# Lin-reg.net
KiCad netlist of a schematic drawn in Altium Designer
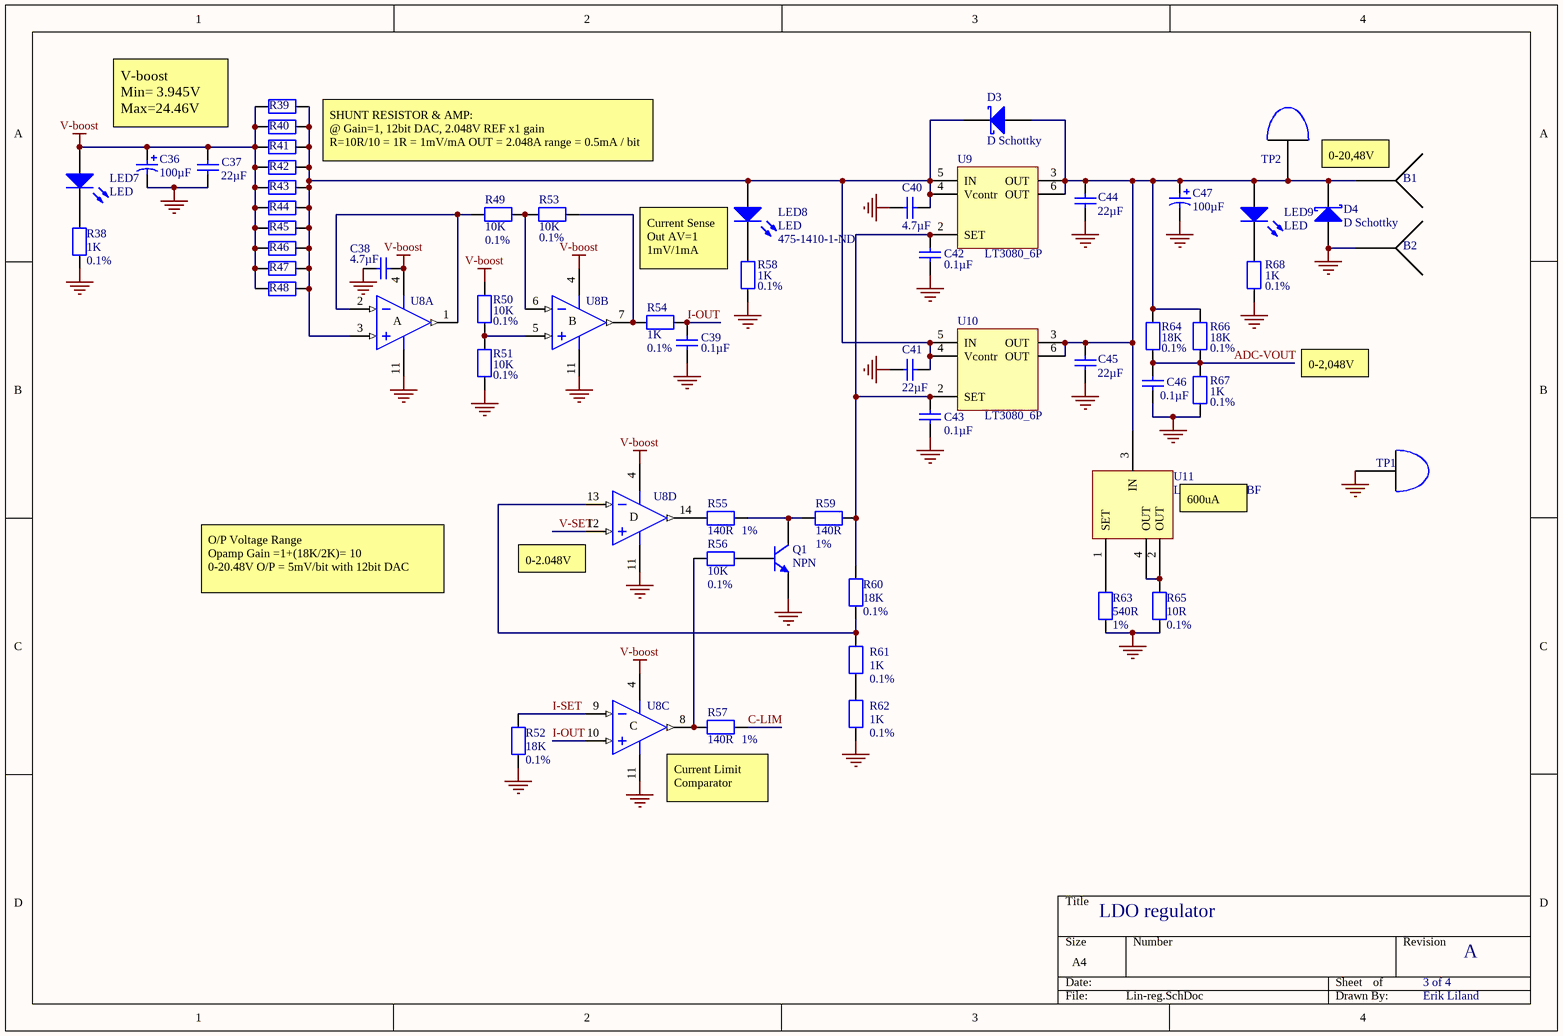
[diagram p0: Lin-reg.SchDoc]

(export (version "E")
  (design (tool "Eeschema 10.0.6"))
  (components
    (comp (ref "B1")
      (value "Banana socket pcb")
      (footprint "BatteruPSU:PCB Banana jack red")
      (description "2.54mm skrew terminal")
      (libsource (lib "BatteryPSU-parts") (part "Banana socket pcb"))
    )
    (comp (ref "B2")
      (value "Banana socket pcb")
      (footprint "BatteruPSU:PCB Banana jack black")
      (description "2.54mm skrew terminal")
      (libsource (lib "BatteryPSU-parts") (part "Banana socket pcb"))
    )
    (comp (ref "C36")
      (value "100µF")
      (footprint "BatteruPSU:CAP SMD (F)")
      (description "Polarized Capacitor")
      (fields
        (field (name "MANUFACTURER") "Panasonic Electronic Components")
        (field (name "MANUFACTURER PART NUMBER") "EEH-ZA1H101P")
      )
      (libsource (lib "BatteryPSU-parts") (part "Cap Pol"))
    )
    (comp (ref "C37")
      (value "22µF")
      (footprint "BatteruPSU:0805_N_CAP")
      (description "Capacitor")
      (fields
        (field (name "MANUFACTURER") "TDK Corporation")
        (field (name "MANUFACTURER PART NUMBER") "C2012X5R1V226M125AC")
      )
      (libsource (lib "BatteryPSU-parts") (part "Cap"))
    )
    (comp (ref "C38")
      (value "4.7µF")
      (footprint "BatteruPSU:0805_N_CAP")
      (description "Capacitor")
      (fields
        (field (name "MANUFACTURER") "Samsung Electro-Mechanics America, Inc")
        (field (name "MANUFACTURER PART NUMBER") "CL21B475KOFNFNE")
      )
      (libsource (lib "BatteryPSU-parts") (part "Cap"))
    )
    (comp (ref "C39")
      (value "0.1µF")
      (footprint "BatteruPSU:0805_N_CAP")
      (description "Capacitor")
      (fields
        (field (name "MANUFACTURER") "Kemet")
        (field (name "MANUFACTURER PART NUMBER") "C0805C104K4RACTU")
      )
      (libsource (lib "BatteryPSU-parts") (part "Cap"))
    )
    (comp (ref "C40")
      (value "4.7µF")
      (footprint "BatteruPSU:0805_N_CAP")
      (description "Capacitor")
      (fields
        (field (name "MANUFACTURER") "Samsung Electro-Mechanics America, Inc")
        (field (name "MANUFACTURER PART NUMBER") "CL21B475KOFNFNE")
      )
      (libsource (lib "BatteryPSU-parts") (part "Cap"))
    )
    (comp (ref "C41")
      (value "22µF")
      (footprint "BatteruPSU:0805_N_CAP")
      (description "Capacitor")
      (fields
        (field (name "MANUFACTURER") "TDK Corporation")
        (field (name "MANUFACTURER PART NUMBER") "C2012X5R1V226M125AC")
      )
      (libsource (lib "BatteryPSU-parts") (part "Cap"))
    )
    (comp (ref "C42")
      (value "0.1µF")
      (footprint "BatteruPSU:0805_N_CAP")
      (description "Capacitor")
      (fields
        (field (name "MANUFACTURER") "Kemet")
        (field (name "MANUFACTURER PART NUMBER") "C0805C104K4RACTU")
      )
      (libsource (lib "BatteryPSU-parts") (part "Cap"))
    )
    (comp (ref "C43")
      (value "0.1µF")
      (footprint "BatteruPSU:0805_N_CAP")
      (description "Capacitor")
      (fields
        (field (name "MANUFACTURER") "Kemet")
        (field (name "MANUFACTURER PART NUMBER") "C0805C104K4RACTU")
      )
      (libsource (lib "BatteryPSU-parts") (part "Cap"))
    )
    (comp (ref "C44")
      (value "22µF")
      (footprint "BatteruPSU:0805_N_CAP")
      (description "Capacitor")
      (fields
        (field (name "MANUFACTURER") "TDK Corporation")
        (field (name "MANUFACTURER PART NUMBER") "C2012X5R1V226M125AC")
      )
      (libsource (lib "BatteryPSU-parts") (part "Cap"))
    )
    (comp (ref "C45")
      (value "22µF")
      (footprint "BatteruPSU:0805_N_CAP")
      (description "Capacitor")
      (fields
        (field (name "MANUFACTURER") "TDK Corporation")
        (field (name "MANUFACTURER PART NUMBER") "C2012X5R1V226M125AC")
      )
      (libsource (lib "BatteryPSU-parts") (part "Cap"))
    )
    (comp (ref "C46")
      (value "0.1µF")
      (footprint "BatteruPSU:0805_N_CAP")
      (description "Capacitor")
      (fields
        (field (name "MANUFACTURER") "Kemet")
        (field (name "MANUFACTURER PART NUMBER") "C0805C104K4RACTU")
      )
      (libsource (lib "BatteryPSU-parts") (part "Cap"))
    )
    (comp (ref "C47")
      (value "100µF")
      (footprint "BatteruPSU:CAP SMD (F)")
      (description "Polarized Capacitor")
      (fields
        (field (name "MANUFACTURER") "Panasonic Electronic Components")
        (field (name "MANUFACTURER PART NUMBER") "EEH-ZA1H101P")
      )
      (libsource (lib "BatteryPSU-parts") (part "Cap Pol"))
    )
    (comp (ref "D3")
      (value "D Schottky")
      (footprint "DO-214AC, SMA")
      (description "Schottky Diode")
      (fields
        (field (name "MANUFACTURER") "Micro Commercial Co")
        (field (name "MANUFACTURER PART NUMBER") "SK33A-TP")
        (field (name "PUBLISHER") "Altium Limited")
      )
      (libsource (lib "BatteryPSU-parts") (part "D Schottky"))
    )
    (comp (ref "D4")
      (value "D Schottky")
      (footprint "DO-214AC, SMA")
      (description "Schottky Diode")
      (fields
        (field (name "MANUFACTURER") "Micro Commercial Co")
        (field (name "MANUFACTURER PART NUMBER") "SK33A-TP")
        (field (name "PUBLISHER") "Altium Limited")
      )
      (libsource (lib "BatteryPSU-parts") (part "D Schottky"))
    )
    (comp (ref "LED7")
      (value "LED")
      (footprint "BatteruPSU:0805_N_LED")
      (description "Typical RED, GREEN, YELLOW, AMBER")
      (fields
        (field (name "MANUFACTURER") "OSRAM Opto Semiconductors Inc")
        (field (name "MANUFACTURER PART NUMBER") "LG R971-KN-1")
      )
      (libsource (lib "BatteryPSU-parts") (part "LED"))
    )
    (comp (ref "LED8")
      (value "LED")
      (footprint "BatteruPSU:0805_N_LED")
      (description "Typical RED, GREEN, YELLOW, AMBER")
      (fields
        (field (name "SUPPLIER PART NUMBER 1") "475-1410-1-ND")
        (field (name "MANUFACTURER") "OSRAM Opto Semiconductors Inc")
        (field (name "MANUFACTURER PART NUMBER") "LG R971-KN-1")
      )
      (libsource (lib "BatteryPSU-parts") (part "LED"))
    )
    (comp (ref "LED9")
      (value "LED")
      (footprint "BatteruPSU:0805_N_LED")
      (description "Typical RED, GREEN, YELLOW, AMBER")
      (fields
        (field (name "MANUFACTURER") "OSRAM Opto Semiconductors Inc")
        (field (name "MANUFACTURER PART NUMBER") "LG R971-KN-1")
      )
      (libsource (lib "BatteryPSU-parts") (part "LED"))
    )
    (comp (ref "Q1")
      (value "NPN")
      (footprint "BatteruPSU:SOT-23_N")
      (description "NPN General Purpose Amplifier")
      (fields
        (field (name "MANUFACTURER") "Micro Commercial Co")
        (field (name "MANUFACTURER PART NUMBER") "MMBT3904-TP")
      )
      (libsource (lib "BatteryPSU-parts") (part "NPN Transistor"))
    )
    (comp (ref "R38")
      (value "1K")
      (footprint "BatteruPSU:0805_N_RES")
      (description "Resistor")
      (fields
        (field (name "TOLERANCE") "0.1%")
        (field (name "MANUFACTURER") "Panasonic Electronic Components")
        (field (name "MANUFACTURER PART NUMBER") "ERA-6AEB102V")
      )
      (libsource (lib "") (part "Res_3"))
    )
    (comp (ref "R39")
      (value "10R")
      (footprint "BatteruPSU:0805_N_RES")
      (description "Resistor")
      (fields
        (field (name "TOLERANCE") "0.1%")
        (field (name "MANUFACTURER") "TE Connectivity AMP Connectors")
      )
      (libsource (lib "") (part "Res_2"))
    )
    (comp (ref "R40")
      (value "10R")
      (footprint "BatteruPSU:0805_N_RES")
      (description "Resistor")
      (fields
        (field (name "TOLERANCE") "0.1%")
        (field (name "MANUFACTURER") "TE Connectivity AMP Connectors")
      )
      (libsource (lib "") (part "Res_2"))
    )
    (comp (ref "R41")
      (value "10R")
      (footprint "BatteruPSU:0805_N_RES")
      (description "Resistor")
      (fields
        (field (name "TOLERANCE") "0.1%")
        (field (name "MANUFACTURER") "TE Connectivity AMP Connectors")
      )
      (libsource (lib "") (part "Res_2"))
    )
    (comp (ref "R42")
      (value "10R")
      (footprint "BatteruPSU:0805_N_RES")
      (description "Resistor")
      (fields
        (field (name "TOLERANCE") "0.1%")
        (field (name "MANUFACTURER") "TE Connectivity AMP Connectors")
      )
      (libsource (lib "") (part "Res_2"))
    )
    (comp (ref "R43")
      (value "10R")
      (footprint "BatteruPSU:0805_N_RES")
      (description "Resistor")
      (fields
        (field (name "TOLERANCE") "0.1%")
        (field (name "MANUFACTURER") "TE Connectivity AMP Connectors")
      )
      (libsource (lib "") (part "Res_2"))
    )
    (comp (ref "R44")
      (value "10R")
      (footprint "BatteruPSU:0805_N_RES")
      (description "Resistor")
      (fields
        (field (name "TOLERANCE") "0.1%")
        (field (name "MANUFACTURER") "TE Connectivity AMP Connectors")
      )
      (libsource (lib "") (part "Res_2"))
    )
    (comp (ref "R45")
      (value "10R")
      (footprint "BatteruPSU:0805_N_RES")
      (description "Resistor")
      (fields
        (field (name "TOLERANCE") "0.1%")
        (field (name "MANUFACTURER") "TE Connectivity AMP Connectors")
      )
      (libsource (lib "") (part "Res_2"))
    )
    (comp (ref "R46")
      (value "10R")
      (footprint "BatteruPSU:0805_N_RES")
      (description "Resistor")
      (fields
        (field (name "TOLERANCE") "0.1%")
        (field (name "MANUFACTURER") "TE Connectivity AMP Connectors")
      )
      (libsource (lib "") (part "Res_2"))
    )
    (comp (ref "R47")
      (value "10R")
      (footprint "BatteruPSU:0805_N_RES")
      (description "Resistor")
      (fields
        (field (name "TOLERANCE") "0.1%")
        (field (name "MANUFACTURER") "TE Connectivity AMP Connectors")
      )
      (libsource (lib "") (part "Res_2"))
    )
    (comp (ref "R48")
      (value "10R")
      (footprint "BatteruPSU:0805_N_RES")
      (description "Resistor")
      (fields
        (field (name "TOLERANCE") "0.1%")
        (field (name "MANUFACTURER") "TE Connectivity AMP Connectors")
      )
      (libsource (lib "") (part "Res_2"))
    )
    (comp (ref "R49")
      (value "10K")
      (footprint "BatteruPSU:0805_N_RES")
      (description "Resistor")
      (fields
        (field (name "TOLERANCE") "0.1%")
        (field (name "MANUFACTURER") "TE Connectivity AMP Connectors")
        (field (name "MANUFACTURER PART NUMBER") "8-1614884-4")
      )
      (libsource (lib "") (part "Res_1"))
    )
    (comp (ref "R50")
      (value "10K")
      (footprint "BatteruPSU:0805_N_RES")
      (description "Resistor")
      (fields
        (field (name "TOLERANCE") "0.1%")
        (field (name "MANUFACTURER") "TE Connectivity AMP Connectors")
        (field (name "MANUFACTURER PART NUMBER") "8-1614884-4")
      )
      (libsource (lib "") (part "Res_3"))
    )
    (comp (ref "R51")
      (value "10K")
      (footprint "BatteruPSU:0805_N_RES")
      (description "Resistor")
      (fields
        (field (name "TOLERANCE") "0.1%")
        (field (name "MANUFACTURER") "TE Connectivity AMP Connectors")
        (field (name "MANUFACTURER PART NUMBER") "8-1614884-4")
      )
      (libsource (lib "") (part "Res_3"))
    )
    (comp (ref "R52")
      (value "18K")
      (footprint "BatteruPSU:0805_N_RES")
      (description "Resistor")
      (fields
        (field (name "TOLERANCE") "0.1%")
        (field (name "MANUFACTURER") "Panasonic Electronic Components")
        (field (name "MANUFACTURER PART NUMBER") "ERA-6AEB183V")
      )
      (libsource (lib "") (part "Res_3"))
    )
    (comp (ref "R53")
      (value "10K")
      (footprint "BatteruPSU:0805_N_RES")
      (description "Resistor")
      (fields
        (field (name "TOLERANCE") "0.1%")
        (field (name "MANUFACTURER") "TE Connectivity AMP Connectors")
        (field (name "MANUFACTURER PART NUMBER") "8-1614884-4")
      )
      (libsource (lib "") (part "Res_1"))
    )
    (comp (ref "R54")
      (value "1K")
      (footprint "BatteruPSU:0805_N_RES")
      (description "Resistor")
      (fields
        (field (name "TOLERANCE") "0.1%")
        (field (name "MANUFACTURER") "Panasonic Electronic Components")
        (field (name "MANUFACTURER PART NUMBER") "ERA-6AEB102V")
      )
      (libsource (lib "") (part "Res_2"))
    )
    (comp (ref "R55")
      (value "140R")
      (footprint "BatteruPSU:0805_N_RES")
      (description "Resistor")
      (fields
        (field (name "TOLERANCE") "1%")
        (field (name "MANUFACTURER") "Samsung Electro-Mechanics America, Inc")
        (field (name "MANUFACTURER PART NUMBER") "RC2012F1400CS")
      )
      (libsource (lib "") (part "Res_1"))
    )
    (comp (ref "R56")
      (value "10K")
      (footprint "BatteruPSU:0805_N_RES")
      (description "Resistor")
      (fields
        (field (name "TOLERANCE") "0.1%")
        (field (name "MANUFACTURER") "TE Connectivity AMP Connectors")
        (field (name "MANUFACTURER PART NUMBER") "8-1614884-4")
      )
      (libsource (lib "") (part "Res_2"))
    )
    (comp (ref "R57")
      (value "140R")
      (footprint "BatteruPSU:0805_N_RES")
      (description "Resistor")
      (fields
        (field (name "TOLERANCE") "1%")
        (field (name "MANUFACTURER") "Samsung Electro-Mechanics America, Inc")
        (field (name "MANUFACTURER PART NUMBER") "RC2012F1400CS")
      )
      (libsource (lib "") (part "Res_1"))
    )
    (comp (ref "R58")
      (value "1K")
      (footprint "BatteruPSU:0805_N_RES")
      (description "Resistor")
      (fields
        (field (name "TOLERANCE") "0.1%")
        (field (name "MANUFACTURER") "Panasonic Electronic Components")
        (field (name "MANUFACTURER PART NUMBER") "ERA-6AEB102V")
      )
      (libsource (lib "BatteryPSU-parts") (part "Res"))
    )
    (comp (ref "R59")
      (value "140R")
      (footprint "BatteruPSU:0805_N_RES")
      (description "Resistor")
      (fields
        (field (name "TOLERANCE") "1%")
        (field (name "MANUFACTURER") "Samsung Electro-Mechanics America, Inc")
        (field (name "MANUFACTURER PART NUMBER") "RC2012F1400CS")
      )
      (libsource (lib "") (part "Res_1"))
    )
    (comp (ref "R60")
      (value "18K")
      (footprint "BatteruPSU:0805_N_RES")
      (description "Resistor")
      (fields
        (field (name "TOLERANCE") "0.1%")
        (field (name "MANUFACTURER") "Panasonic Electronic Components")
        (field (name "MANUFACTURER PART NUMBER") "ERA-6AEB183V")
      )
      (libsource (lib "BatteryPSU-parts") (part "Res"))
    )
    (comp (ref "R61")
      (value "1K")
      (footprint "BatteruPSU:0805_N_RES")
      (description "Resistor")
      (fields
        (field (name "TOLERANCE") "0.1%")
        (field (name "MANUFACTURER") "Panasonic Electronic Components")
        (field (name "MANUFACTURER PART NUMBER") "ERA-6AEB102V")
      )
      (libsource (lib "BatteryPSU-parts") (part "Res"))
    )
    (comp (ref "R62")
      (value "1K")
      (footprint "BatteruPSU:0805_N_RES")
      (description "Resistor")
      (fields
        (field (name "TOLERANCE") "0.1%")
        (field (name "MANUFACTURER") "Panasonic Electronic Components")
        (field (name "MANUFACTURER PART NUMBER") "ERA-6AEB102V")
      )
      (libsource (lib "BatteryPSU-parts") (part "Res"))
    )
    (comp (ref "R63")
      (value "540R")
      (footprint "BatteruPSU:0805_N_RES")
      (description "Resistor")
      (fields (field (name "TOLERANCE") "1%"))
      (libsource (lib "") (part "Res_3"))
    )
    (comp (ref "R64")
      (value "18K")
      (footprint "BatteruPSU:0805_N_RES")
      (description "Resistor")
      (fields
        (field (name "TOLERANCE") "0.1%")
        (field (name "MANUFACTURER") "Panasonic Electronic Components")
        (field (name "MANUFACTURER PART NUMBER") "ERA-6AEB183V")
      )
      (libsource (lib "BatteryPSU-parts") (part "Res"))
    )
    (comp (ref "R65")
      (value "10R")
      (footprint "BatteruPSU:0805_N_RES")
      (description "Resistor")
      (fields
        (field (name "TOLERANCE") "0.1%")
        (field (name "MANUFACTURER") "TE Connectivity AMP Connectors")
        (field (name "MANUFACTURER PART NUMBER") "2-1625868-7")
      )
      (libsource (lib "BatteryPSU-parts") (part "Res"))
    )
    (comp (ref "R66")
      (value "18K")
      (footprint "BatteruPSU:0805_N_RES")
      (description "Resistor")
      (fields
        (field (name "TOLERANCE") "0.1%")
        (field (name "MANUFACTURER") "Panasonic Electronic Components")
        (field (name "MANUFACTURER PART NUMBER") "ERA-6AEB183V")
      )
      (libsource (lib "BatteryPSU-parts") (part "Res"))
    )
    (comp (ref "R67")
      (value "1K")
      (footprint "BatteruPSU:0805_N_RES")
      (description "Resistor")
      (fields
        (field (name "TOLERANCE") "0.1%")
        (field (name "MANUFACTURER") "Panasonic Electronic Components")
        (field (name "MANUFACTURER PART NUMBER") "ERA-6AEB102V")
      )
      (libsource (lib "BatteryPSU-parts") (part "Res"))
    )
    (comp (ref "R68")
      (value "1K")
      (footprint "BatteruPSU:0805_N_RES")
      (description "Resistor")
      (fields
        (field (name "TOLERANCE") "0.1%")
        (field (name "MANUFACTURER") "Panasonic Electronic Components")
        (field (name "MANUFACTURER PART NUMBER") "ERA-6AEB102V")
      )
      (libsource (lib "BatteryPSU-parts") (part "Res"))
    )
    (comp (ref "TP1")
      (value "Test-point")
      (footprint "BatteruPSU:Test point")
      (libsource (lib "BatteryPSU-parts") (part "Test point"))
    )
    (comp (ref "TP2")
      (value "Test-point")
      (footprint "BatteruPSU:Test point")
      (libsource (lib "") (part "Test point_1"))
    )
    (comp (ref "U8")
      (value "BA2902FV")
      (footprint "BatteruPSU:TSSOP14_N")
      (description "Quad Low-Power Operational Amplifier")
      (fields
        (field (name "MANUFACTURER") "Rohm Semiconductor")
        (field (name "MANUFACTURER PART NUMBER") "BA2902FV-E2")
      )
      (libsource (lib "BatteryPSU-parts") (part "BA2902FV"))
    )
    (comp (ref "U9")
      (value "LT3080_6P")
      (footprint "BatteruPSU:DD-PAK-5_N_HEATSINK")
      (description "LT3080 LDO regulator")
      (fields
        (field (name "MANUFACTURER") "Linear Technology")
        (field (name "MANUFACTURER PART NUMBER") "LT3080EQ#PBF")
      )
      (libsource (lib "BatteryPSU-parts") (part "LT3080_6P"))
    )
    (comp (ref "U10")
      (value "LT3080_6P")
      (footprint "BatteruPSU:DD-PAK-5_N_HEATSINK")
      (description "LT3080 LDO regulator")
      (fields
        (field (name "MANUFACTURER") "Linear Technology")
        (field (name "MANUFACTURER PART NUMBER") "LT3080EQ#PBF")
      )
      (libsource (lib "BatteryPSU-parts") (part "LT3080_6P"))
    )
    (comp (ref "U11")
      (value "LT3092EST#PBF")
      (footprint "BatteruPSU:SOT223_N")
      (description "Current source")
      (fields (field (name "MANUFACTURER") "Linear Technology"))
      (libsource (lib "BatteryPSU-parts") (part "LT3092"))
    )
  )
  (nets
    (net (code "1") (name "/ADC-VOUT") (class "Default")
      (node (ref "C46") (pin "2") (pinfunction "2_2") (pintype "passive"))
      (node (ref "R64") (pin "2") (pinfunction "2_2") (pintype "passive"))
      (node (ref "R66") (pin "2") (pinfunction "2_2") (pintype "passive"))
      (node (ref "R67") (pin "1") (pinfunction "1_1") (pintype "passive"))
    )
    (net (code "2") (name "/C-LIM") (class "Default")
      (node (ref "R57") (pin "2") (pinfunction "2_2") (pintype "passive"))
    )
    (net (code "3") (name "/I-OUT") (class "Default")
      (node (ref "C39") (pin "2") (pinfunction "2_2") (pintype "passive"))
      (node (ref "R54") (pin "1") (pinfunction "1_1") (pintype "passive"))
      (node (ref "U8") (pin "10") (pinfunction "+IN3_10") (pintype "input"))
    )
    (net (code "4") (name "/I-SET") (class "Default")
      (node (ref "R52") (pin "2") (pinfunction "2_2") (pintype "passive"))
      (node (ref "U8") (pin "9") (pinfunction "-IN3_9") (pintype "input"))
    )
    (net (code "5") (name "/V-SET") (class "Default")
      (node (ref "U8") (pin "12") (pinfunction "+IN4_12") (pintype "input"))
    )
    (net (code "6") (name "GND") (class "Default")
      (node (ref "B2") (pin "1") (pintype "passive"))
      (node (ref "C36") (pin "2") (pinfunction "2_2") (pintype "passive"))
      (node (ref "C37") (pin "2") (pinfunction "2_2") (pintype "passive"))
      (node (ref "C38") (pin "1") (pinfunction "1_1") (pintype "passive"))
      (node (ref "C39") (pin "1") (pinfunction "1_1") (pintype "passive"))
      (node (ref "C40") (pin "2") (pinfunction "2_2") (pintype "passive"))
      (node (ref "C41") (pin "2") (pinfunction "2_2") (pintype "passive"))
      (node (ref "C42") (pin "1") (pinfunction "1_1") (pintype "passive"))
      (node (ref "C43") (pin "1") (pinfunction "1_1") (pintype "passive"))
      (node (ref "C44") (pin "2") (pinfunction "2_2") (pintype "passive"))
      (node (ref "C45") (pin "2") (pinfunction "2_2") (pintype "passive"))
      (node (ref "C46") (pin "1") (pinfunction "1_1") (pintype "passive"))
      (node (ref "C47") (pin "2") (pinfunction "2_2") (pintype "passive"))
      (node (ref "D4") (pin "1") (pinfunction "A_1") (pintype "passive"))
      (node (ref "Q1") (pin "2") (pinfunction "E_2") (pintype "passive"))
      (node (ref "R38") (pin "1") (pinfunction "1_1") (pintype "passive"))
      (node (ref "R51") (pin "1") (pinfunction "1_1") (pintype "passive"))
      (node (ref "R52") (pin "1") (pinfunction "1_1") (pintype "passive"))
      (node (ref "R58") (pin "2") (pinfunction "2_2") (pintype "passive"))
      (node (ref "R62") (pin "2") (pinfunction "2_2") (pintype "passive"))
      (node (ref "R63") (pin "1") (pinfunction "1_1") (pintype "passive"))
      (node (ref "R65") (pin "2") (pinfunction "2_2") (pintype "passive"))
      (node (ref "R67") (pin "2") (pinfunction "2_2") (pintype "passive"))
      (node (ref "R68") (pin "2") (pinfunction "2_2") (pintype "passive"))
      (node (ref "TP1") (pin "1") (pinfunction "TP_1") (pintype "passive"))
      (node (ref "U8") (pin "11") (pinfunction "VEE_11") (pintype "passive"))
    )
    (net (code "7") (name "Net-(D3-A)") (class "Default")
      (node (ref "B1") (pin "1") (pintype "passive"))
      (node (ref "C44") (pin "1") (pinfunction "1_1") (pintype "passive"))
      (node (ref "C45") (pin "1") (pinfunction "1_1") (pintype "passive"))
      (node (ref "C47") (pin "1") (pinfunction "1_1") (pintype "passive"))
      (node (ref "D3") (pin "1") (pinfunction "A_1") (pintype "passive"))
      (node (ref "D4") (pin "2") (pinfunction "K_2") (pintype "passive"))
      (node (ref "LED9") (pin "1") (pinfunction "A_1") (pintype "passive"))
      (node (ref "R64") (pin "1") (pinfunction "1_1") (pintype "passive"))
      (node (ref "R66") (pin "1") (pinfunction "1_1") (pintype "passive"))
      (node (ref "TP2") (pin "1") (pinfunction "TP_1") (pintype "passive"))
      (node (ref "U10") (pin "3") (pinfunction "OUT_3") (pintype "passive"))
      (node (ref "U10") (pin "6") (pinfunction "OUT_6") (pintype "passive"))
      (node (ref "U11") (pin "3") (pinfunction "IN_3") (pintype "passive"))
      (node (ref "U9") (pin "3") (pinfunction "OUT_3") (pintype "passive"))
      (node (ref "U9") (pin "6") (pinfunction "OUT_6") (pintype "passive"))
    )
    (net (code "8") (name "Net-(D3-K)") (class "Default")
      (node (ref "C40") (pin "1") (pinfunction "1_1") (pintype "passive"))
      (node (ref "C41") (pin "1") (pinfunction "1_1") (pintype "passive"))
      (node (ref "D3") (pin "2") (pinfunction "K_2") (pintype "passive"))
      (node (ref "LED8") (pin "1") (pinfunction "A_1") (pintype "passive"))
      (node (ref "R39") (pin "1") (pinfunction "1_1") (pintype "passive"))
      (node (ref "R40") (pin "1") (pinfunction "1_1") (pintype "passive"))
      (node (ref "R41") (pin "1") (pinfunction "1_1") (pintype "passive"))
      (node (ref "R42") (pin "1") (pinfunction "1_1") (pintype "passive"))
      (node (ref "R43") (pin "1") (pinfunction "1_1") (pintype "passive"))
      (node (ref "R44") (pin "1") (pinfunction "1_1") (pintype "passive"))
      (node (ref "R45") (pin "1") (pinfunction "1_1") (pintype "passive"))
      (node (ref "R46") (pin "1") (pinfunction "1_1") (pintype "passive"))
      (node (ref "R47") (pin "1") (pinfunction "1_1") (pintype "passive"))
      (node (ref "R48") (pin "1") (pinfunction "1_1") (pintype "passive"))
      (node (ref "U10") (pin "4") (pinfunction "Vcontr_4") (pintype "passive"))
      (node (ref "U10") (pin "5") (pinfunction "IN_5") (pintype "passive"))
      (node (ref "U8") (pin "3") (pinfunction "+IN1_3") (pintype "input"))
      (node (ref "U9") (pin "4") (pinfunction "Vcontr_4") (pintype "passive"))
      (node (ref "U9") (pin "5") (pinfunction "IN_5") (pintype "passive"))
    )
    (net (code "9") (name "Net-(LED7-K)") (class "Default")
      (node (ref "LED7") (pin "2") (pinfunction "K_2") (pintype "passive"))
      (node (ref "R38") (pin "2") (pinfunction "2_2") (pintype "passive"))
    )
    (net (code "10") (name "Net-(LED8-K)") (class "Default")
      (node (ref "LED8") (pin "2") (pinfunction "K_2") (pintype "passive"))
      (node (ref "R58") (pin "1") (pinfunction "1_1") (pintype "passive"))
    )
    (net (code "11") (name "Net-(LED9-K)") (class "Default")
      (node (ref "LED9") (pin "2") (pinfunction "K_2") (pintype "passive"))
      (node (ref "R68") (pin "1") (pinfunction "1_1") (pintype "passive"))
    )
    (net (code "12") (name "Net-(Q1-B)") (class "Default")
      (node (ref "Q1") (pin "1") (pinfunction "B_1") (pintype "passive"))
      (node (ref "R56") (pin "1") (pinfunction "1_1") (pintype "passive"))
    )
    (net (code "13") (name "Net-(Q1-C)") (class "Default")
      (node (ref "Q1") (pin "3") (pinfunction "C_3") (pintype "passive"))
      (node (ref "R55") (pin "2") (pinfunction "2_2") (pintype "passive"))
      (node (ref "R59") (pin "1") (pinfunction "1_1") (pintype "passive"))
    )
    (net (code "14") (name "Net-(R61-Pad2)") (class "Default")
      (node (ref "R61") (pin "2") (pinfunction "2_2") (pintype "passive"))
      (node (ref "R62") (pin "1") (pinfunction "1_1") (pintype "passive"))
    )
    (net (code "15") (name "Net-(R65-Pad1)") (class "Default")
      (node (ref "R65") (pin "1") (pinfunction "1_1") (pintype "passive"))
      (node (ref "U11") (pin "2") (pinfunction "OUT_2") (pintype "passive"))
      (node (ref "U11") (pin "4") (pinfunction "OUT_4") (pintype "passive"))
    )
    (net (code "16") (name "Net-(U8A--IN1)") (class "Default")
      (node (ref "R49") (pin "1") (pinfunction "1_1") (pintype "passive"))
      (node (ref "U8") (pin "1") (pinfunction "OUT1_1") (pintype "output"))
      (node (ref "U8") (pin "2") (pinfunction "-IN1_2") (pintype "input"))
    )
    (net (code "17") (name "Net-(U8B-+IN2)") (class "Default")
      (node (ref "R50") (pin "1") (pinfunction "1_1") (pintype "passive"))
      (node (ref "R51") (pin "2") (pinfunction "2_2") (pintype "passive"))
      (node (ref "U8") (pin "5") (pinfunction "+IN2_5") (pintype "input"))
    )
    (net (code "18") (name "Net-(U8B--IN2)") (class "Default")
      (node (ref "R49") (pin "2") (pinfunction "2_2") (pintype "passive"))
      (node (ref "R53") (pin "1") (pinfunction "1_1") (pintype "passive"))
      (node (ref "U8") (pin "6") (pinfunction "-IN2_6") (pintype "input"))
    )
    (net (code "19") (name "Net-(U8B-OUT2)") (class "Default")
      (node (ref "R53") (pin "2") (pinfunction "2_2") (pintype "passive"))
      (node (ref "R54") (pin "2") (pinfunction "2_2") (pintype "passive"))
      (node (ref "U8") (pin "7") (pinfunction "OUT2_7") (pintype "output"))
    )
    (net (code "20") (name "Net-(U8C-OUT3)") (class "Default")
      (node (ref "R56") (pin "2") (pinfunction "2_2") (pintype "passive"))
      (node (ref "R57") (pin "1") (pinfunction "1_1") (pintype "passive"))
      (node (ref "U8") (pin "8") (pinfunction "OUT3_8") (pintype "output"))
    )
    (net (code "21") (name "Net-(U8D--IN4)") (class "Default")
      (node (ref "R60") (pin "2") (pinfunction "2_2") (pintype "passive"))
      (node (ref "R61") (pin "1") (pinfunction "1_1") (pintype "passive"))
      (node (ref "U8") (pin "13") (pinfunction "-IN4_13") (pintype "input"))
    )
    (net (code "22") (name "Net-(U8D-OUT4)") (class "Default")
      (node (ref "R55") (pin "1") (pinfunction "1_1") (pintype "passive"))
      (node (ref "U8") (pin "14") (pinfunction "OUT4_14") (pintype "output"))
    )
    (net (code "23") (name "Net-(U10-SET)") (class "Default")
      (node (ref "C42") (pin "2") (pinfunction "2_2") (pintype "passive"))
      (node (ref "C43") (pin "2") (pinfunction "2_2") (pintype "passive"))
      (node (ref "R59") (pin "2") (pinfunction "2_2") (pintype "passive"))
      (node (ref "R60") (pin "1") (pinfunction "1_1") (pintype "passive"))
      (node (ref "U10") (pin "2") (pinfunction "SET_2") (pintype "passive"))
      (node (ref "U9") (pin "2") (pinfunction "SET_2") (pintype "passive"))
    )
    (net (code "24") (name "Net-(U11-SET)") (class "Default")
      (node (ref "R63") (pin "2") (pinfunction "2_2") (pintype "passive"))
      (node (ref "U11") (pin "1") (pinfunction "SET_1") (pintype "passive"))
    )
    (net (code "25") (name "V-boost") (class "Default")
      (node (ref "C36") (pin "1") (pinfunction "1_1") (pintype "passive"))
      (node (ref "C37") (pin "1") (pinfunction "1_1") (pintype "passive"))
      (node (ref "C38") (pin "2") (pinfunction "2_2") (pintype "passive"))
      (node (ref "LED7") (pin "1") (pinfunction "A_1") (pintype "passive"))
      (node (ref "R39") (pin "2") (pinfunction "2_2") (pintype "passive"))
      (node (ref "R40") (pin "2") (pinfunction "2_2") (pintype "passive"))
      (node (ref "R41") (pin "2") (pinfunction "2_2") (pintype "passive"))
      (node (ref "R42") (pin "2") (pinfunction "2_2") (pintype "passive"))
      (node (ref "R43") (pin "2") (pinfunction "2_2") (pintype "passive"))
      (node (ref "R44") (pin "2") (pinfunction "2_2") (pintype "passive"))
      (node (ref "R45") (pin "2") (pinfunction "2_2") (pintype "passive"))
      (node (ref "R46") (pin "2") (pinfunction "2_2") (pintype "passive"))
      (node (ref "R47") (pin "2") (pinfunction "2_2") (pintype "passive"))
      (node (ref "R48") (pin "2") (pinfunction "2_2") (pintype "passive"))
      (node (ref "R50") (pin "2") (pinfunction "2_2") (pintype "passive"))
      (node (ref "U8") (pin "4") (pinfunction "VCC_4") (pintype "power_in"))
    )
  )
)
